# SCH___2022-11-09.net
KiCad netlist of a schematic drawn in EasyEDA
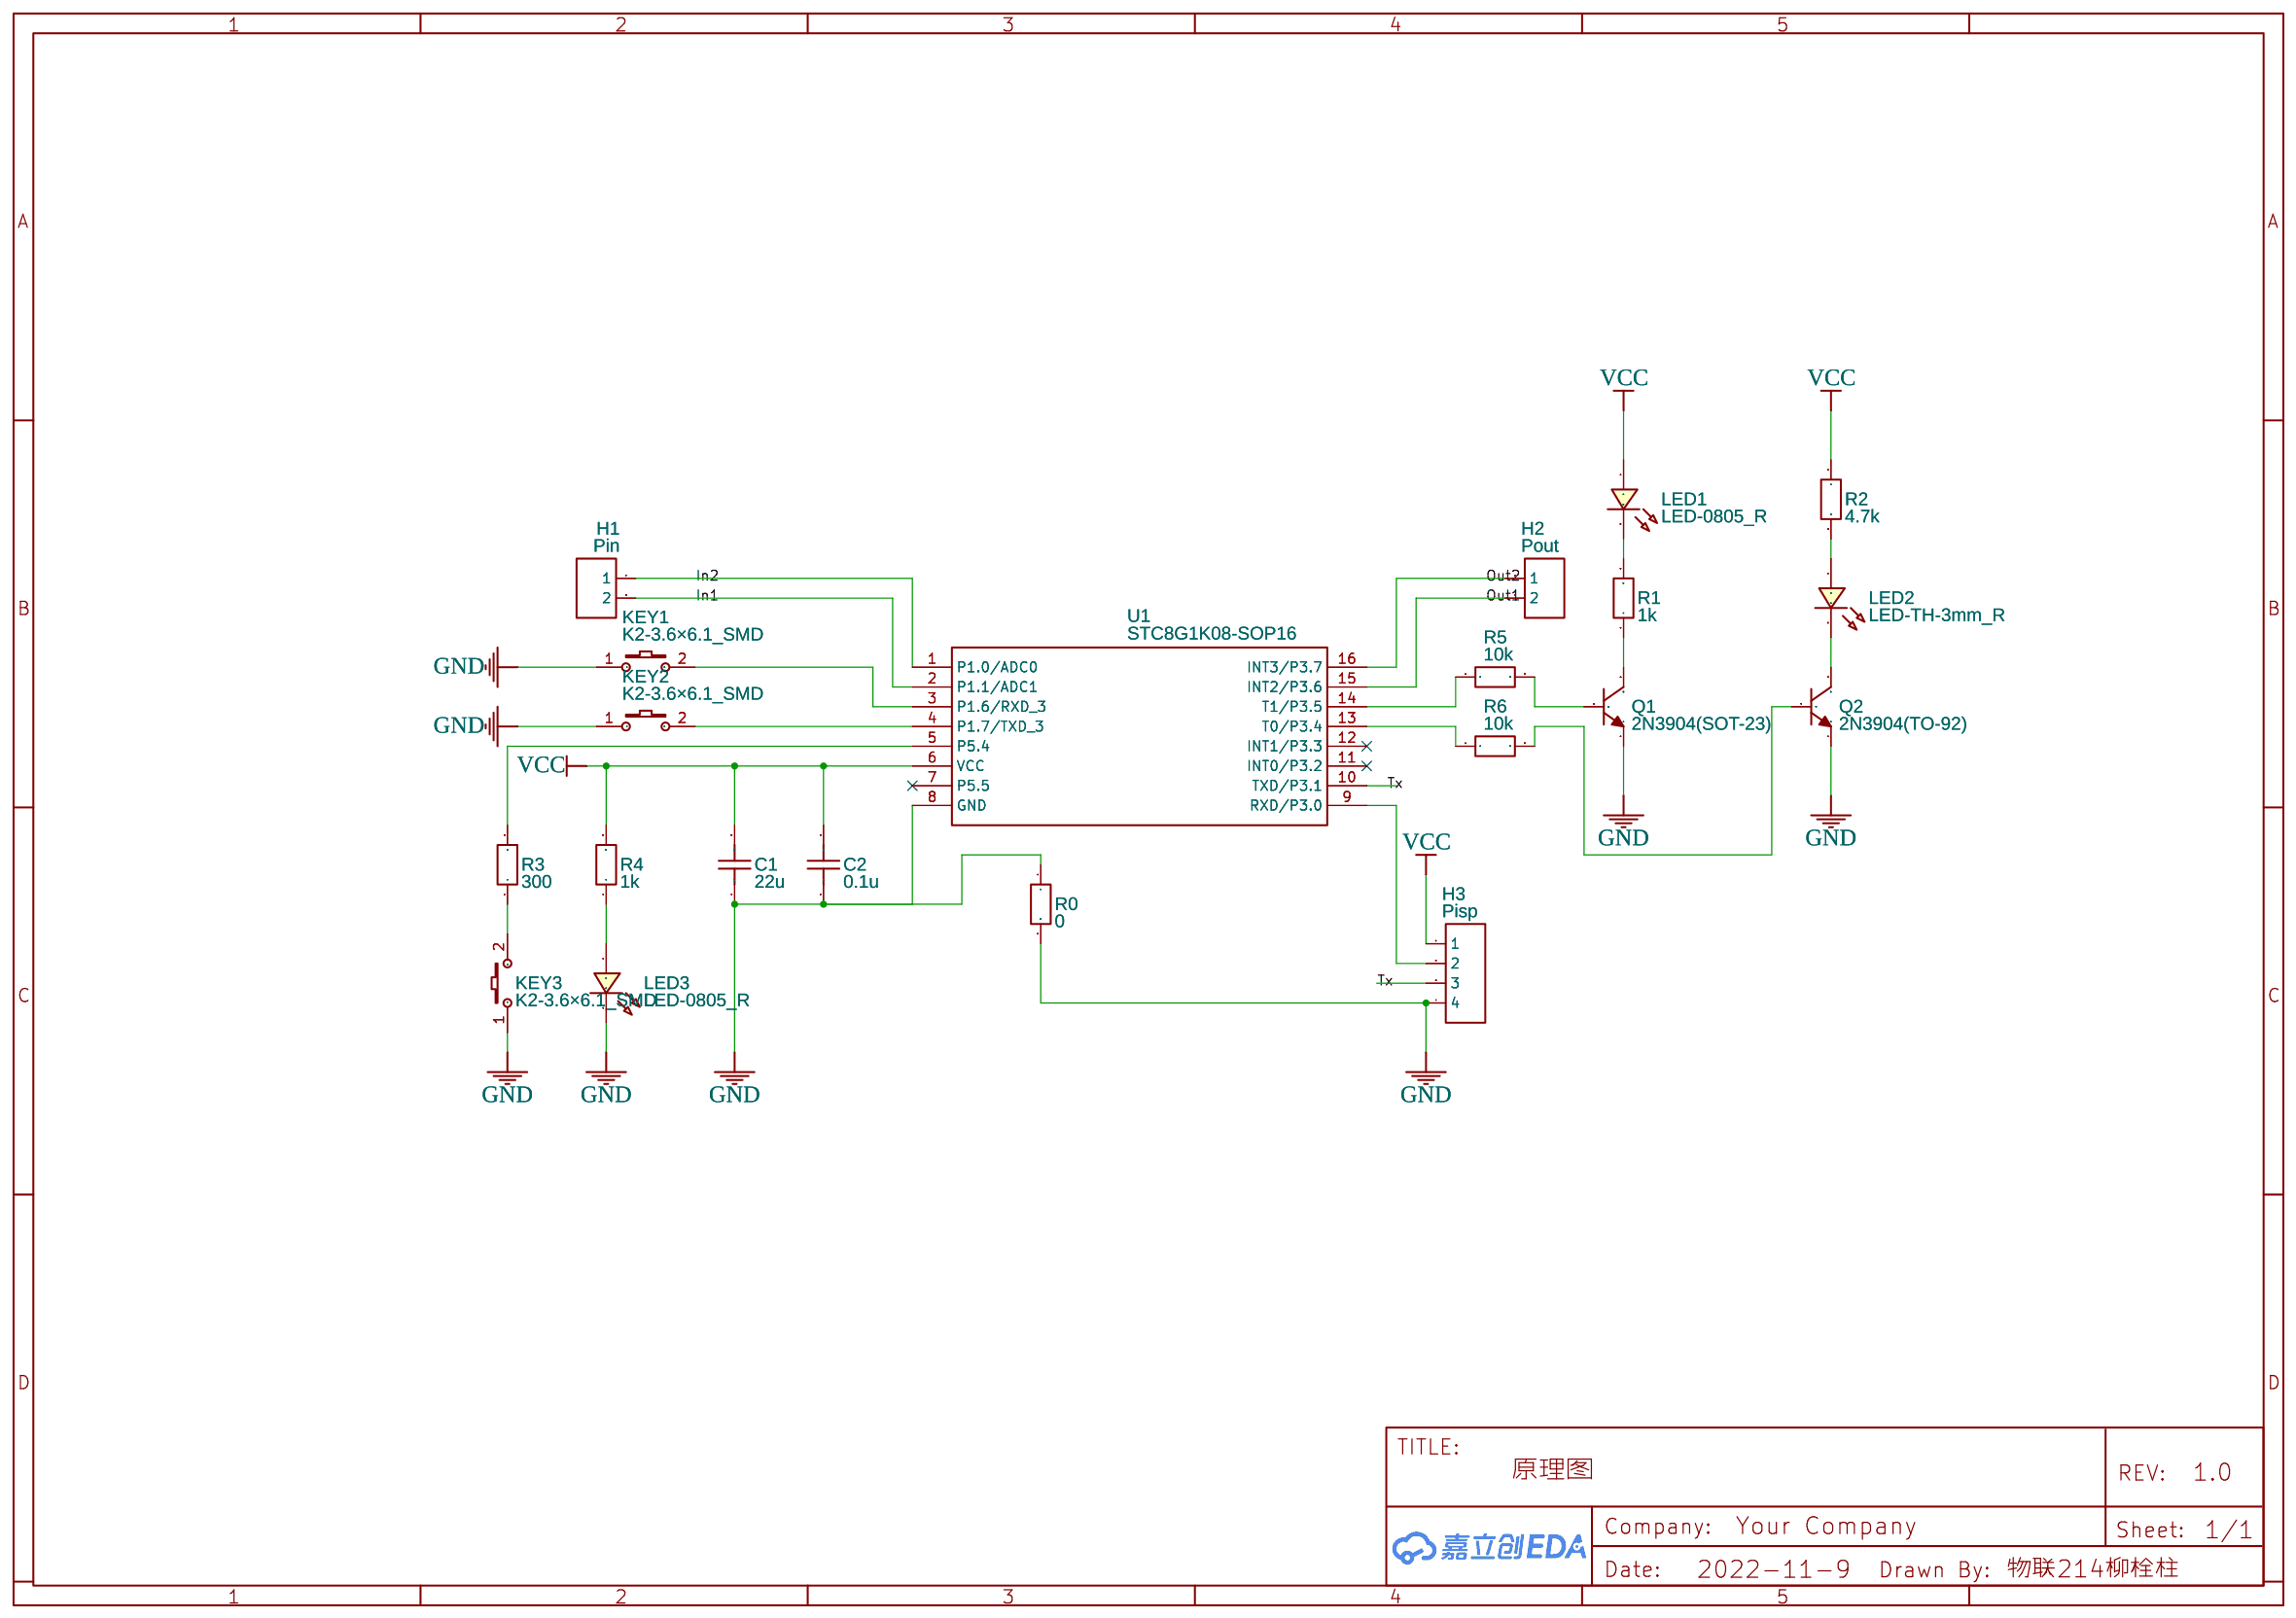
[diagram p0: schematic sheet]

(export (version "E")
  (design (tool "Eeschema 10.0.6"))
  (components
    (comp (ref "C1") (value "22u") (libsource (lib "") (part "C_0603_US")))
    (comp (ref "C2") (value "0.1u") (libsource (lib "") (part "C_0603_US")))
    (comp (ref "H1")
      (value "Pin")
      (fields (field (name "BOM_Supplier Part") "C49661"))
      (libsource (lib "") (part "HDR-F-2.54_1x2_1"))
    )
    (comp (ref "H2")
      (value "Pout")
      (fields (field (name "BOM_Supplier Part") "C49661"))
      (libsource (lib "") (part "HDR-F-2.54_1x2"))
    )
    (comp (ref "H3")
      (value "Pisp")
      (fields (field (name "BOM_Supplier Part") "C225501"))
      (libsource (lib "") (part "HDR-F-2.54_1x4"))
    )
    (comp (ref "KEY1")
      (value "K2-3.6×6.1_SMD")
      (fields
        (field (name "BOM_Manufacturer Part") "K2-1107ST-A4SW-06")
        (field (name "BOM_Supplier Part") "C118141")
      )
      (libsource (lib "") (part "K2-3.6×6.1_SMD_1"))
    )
    (comp (ref "KEY2")
      (value "K2-3.6×6.1_SMD")
      (fields
        (field (name "BOM_Manufacturer Part") "K2-1107ST-A4SW-06")
        (field (name "BOM_Supplier Part") "C118141")
      )
      (libsource (lib "") (part "K2-3.6×6.1_SMD_1"))
    )
    (comp (ref "KEY3")
      (value "K2-3.6×6.1_SMD")
      (fields
        (field (name "BOM_Manufacturer Part") "K2-1107ST-A4SW-06")
        (field (name "BOM_Supplier Part") "C118141")
      )
      (libsource (lib "") (part "K2-3.6×6.1_SMD"))
    )
    (comp (ref "LED1")
      (value "LED-0805_R")
      (fields
        (field (name "BOM_Manufacturer Part") "17-21SURC/S530-A3/TR8")
        (field (name "BOM_Supplier Part") "C72037")
      )
      (libsource (lib "") (part "LED-0805_R"))
    )
    (comp (ref "LED2")
      (value "LED-TH-3mm_R")
      (fields
        (field (name "BOM_Manufacturer Part") "204-10SDRD/S530-A3-L")
        (field (name "BOM_Supplier Part") "C84774")
      )
      (libsource (lib "") (part "LED-TH-3mm_R"))
    )
    (comp (ref "LED3")
      (value "LED-0805_R")
      (fields
        (field (name "BOM_Manufacturer Part") "17-21SURC/S530-A3/TR8")
        (field (name "BOM_Supplier Part") "C72037")
      )
      (libsource (lib "") (part "LED-0805_R"))
    )
    (comp (ref "Q1")
      (value "2N3904(SOT-23)")
      (fields
        (field (name "BOM_Manufacturer Part") "2n3904S-RTK/PS")
        (field (name "BOM_Supplier Part") "C18536")
      )
      (libsource (lib "") (part "2N3904(SOT-23)"))
    )
    (comp (ref "Q2")
      (value "2N3904(TO-92)")
      (fields (field (name "BOM_Manufacturer Part") "2N3904") (field (name "BOM_Supplier Part") "C118538"))
      (libsource (lib "") (part "2N3904(TO-92)"))
    )
    (comp (ref "R0") (value "0") (libsource (lib "") (part "R_0603_EU_1")))
    (comp (ref "R1") (value "1k") (libsource (lib "") (part "R_0603_EU_2")))
    (comp (ref "R2") (value "4.7k") (libsource (lib "") (part "R_0603_EU_1")))
    (comp (ref "R3") (value "300") (libsource (lib "") (part "R_0603_EU_2")))
    (comp (ref "R4") (value "1k") (libsource (lib "") (part "R_0603_EU_2")))
    (comp (ref "R5") (value "10k") (libsource (lib "") (part "R_0603_EU")))
    (comp (ref "R6") (value "10k") (libsource (lib "") (part "R_0603_EU")))
    (comp (ref "U1") (value "STC8G1K08-SOP16") (libsource (lib "") (part "STC8G1K08-SOP16")))
  )
  (nets
    (net (code "1") (name "/In1") (class "Default")
      (node (ref "H1") (pin "2") (pinfunction "2_2") (pintype "input"))
      (node (ref "U1") (pin "2") (pinfunction "P1.1/ADC1_2") (pintype "unspecified"))
    )
    (net (code "2") (name "/In2") (class "Default")
      (node (ref "H1") (pin "1") (pinfunction "1_1") (pintype "input"))
      (node (ref "U1") (pin "1") (pinfunction "P1.0/ADC0_1") (pintype "unspecified"))
    )
    (net (code "3") (name "/Out1") (class "Default")
      (node (ref "H2") (pin "2") (pinfunction "2_2") (pintype "input"))
      (node (ref "U1") (pin "15") (pinfunction "INT2/P3.6_15") (pintype "unspecified"))
    )
    (net (code "4") (name "/Out2") (class "Default")
      (node (ref "H2") (pin "1") (pinfunction "1_1") (pintype "input"))
      (node (ref "U1") (pin "16") (pinfunction "INT3/P3.7_16") (pintype "unspecified"))
    )
    (net (code "5") (name "/Tx") (class "Default")
      (node (ref "H3") (pin "3") (pinfunction "3_3") (pintype "unspecified"))
      (node (ref "U1") (pin "10") (pinfunction "TXD/P3.1_10") (pintype "unspecified"))
    )
    (net (code "6") (name "GND") (class "Default")
      (node (ref "C1") (pin "1") (pinfunction "1_1") (pintype "unspecified"))
      (node (ref "C2") (pin "1") (pinfunction "1_1") (pintype "unspecified"))
      (node (ref "H3") (pin "4") (pinfunction "4_4") (pintype "unspecified"))
      (node (ref "KEY1") (pin "1") (pinfunction "1_1") (pintype "unspecified"))
      (node (ref "KEY2") (pin "1") (pinfunction "1_1") (pintype "unspecified"))
      (node (ref "KEY3") (pin "1") (pinfunction "1_1") (pintype "unspecified"))
      (node (ref "LED3") (pin "2") (pinfunction "2_2") (pintype "unspecified"))
      (node (ref "Q1") (pin "1") (pinfunction "E_1") (pintype "input"))
      (node (ref "Q2") (pin "1") (pinfunction "E_1") (pintype "unspecified"))
      (node (ref "R0") (pin "1") (pinfunction "1_1") (pintype "unspecified"))
      (node (ref "R0") (pin "2") (pinfunction "2_2") (pintype "unspecified"))
      (node (ref "U1") (pin "8") (pinfunction "GND_8") (pintype "unspecified"))
    )
    (net (code "7") (name "Net-(KEY3-Pad2)") (class "Default")
      (node (ref "KEY3") (pin "2") (pinfunction "2_2") (pintype "unspecified"))
      (node (ref "R3") (pin "1") (pinfunction "1_1") (pintype "unspecified"))
    )
    (net (code "8") (name "Net-(LED1-Pad2)") (class "Default")
      (node (ref "LED1") (pin "2") (pinfunction "2_2") (pintype "unspecified"))
      (node (ref "R1") (pin "2") (pinfunction "2_2") (pintype "unspecified"))
    )
    (net (code "9") (name "Net-(LED2-Pad1)") (class "Default")
      (node (ref "LED2") (pin "1") (pinfunction "1_1") (pintype "unspecified"))
      (node (ref "R2") (pin "2") (pinfunction "2_2") (pintype "unspecified"))
    )
    (net (code "10") (name "Net-(LED3-Pad1)") (class "Default")
      (node (ref "LED3") (pin "1") (pinfunction "1_1") (pintype "unspecified"))
      (node (ref "R4") (pin "1") (pinfunction "1_1") (pintype "unspecified"))
    )
    (net (code "11") (name "Net-(Q1-B)") (class "Default")
      (node (ref "Q1") (pin "2") (pinfunction "B_2") (pintype "input"))
      (node (ref "R5") (pin "2") (pinfunction "2_2") (pintype "unspecified"))
    )
    (net (code "12") (name "Net-(Q1-C)") (class "Default")
      (node (ref "Q1") (pin "3") (pinfunction "C_3") (pintype "input"))
      (node (ref "R1") (pin "1") (pinfunction "1_1") (pintype "unspecified"))
    )
    (net (code "13") (name "Net-(Q2-B)") (class "Default")
      (node (ref "Q2") (pin "2") (pinfunction "B_2") (pintype "unspecified"))
      (node (ref "R6") (pin "2") (pinfunction "2_2") (pintype "unspecified"))
    )
    (net (code "14") (name "Net-(Q2-C)") (class "Default")
      (node (ref "LED2") (pin "2") (pinfunction "2_2") (pintype "unspecified"))
      (node (ref "Q2") (pin "3") (pinfunction "C_3") (pintype "unspecified"))
    )
    (net (code "15") (name "Net-(U1-P1.6{slash}RXD_3)") (class "Default")
      (node (ref "KEY1") (pin "2") (pinfunction "2_2") (pintype "unspecified"))
      (node (ref "U1") (pin "3") (pinfunction "P1.6/RXD_3_3") (pintype "unspecified"))
    )
    (net (code "16") (name "Net-(U1-P1.7{slash}TXD_3)") (class "Default")
      (node (ref "KEY2") (pin "2") (pinfunction "2_2") (pintype "unspecified"))
      (node (ref "U1") (pin "4") (pinfunction "P1.7/TXD_3_4") (pintype "unspecified"))
    )
    (net (code "17") (name "Net-(U1-P5.4)") (class "Default")
      (node (ref "R3") (pin "2") (pinfunction "2_2") (pintype "unspecified"))
      (node (ref "U1") (pin "5") (pinfunction "P5.4_5") (pintype "unspecified"))
    )
    (net (code "18") (name "Net-(U1-RXD{slash}P3.0)") (class "Default")
      (node (ref "H3") (pin "2") (pinfunction "2_2") (pintype "unspecified"))
      (node (ref "U1") (pin "9") (pinfunction "RXD/P3.0_9") (pintype "unspecified"))
    )
    (net (code "19") (name "Net-(U1-T0{slash}P3.4)") (class "Default")
      (node (ref "R6") (pin "1") (pinfunction "1_1") (pintype "unspecified"))
      (node (ref "U1") (pin "13") (pinfunction "T0/P3.4_13") (pintype "unspecified"))
    )
    (net (code "20") (name "Net-(U1-T1{slash}P3.5)") (class "Default")
      (node (ref "R5") (pin "1") (pinfunction "1_1") (pintype "unspecified"))
      (node (ref "U1") (pin "14") (pinfunction "T1/P3.5_14") (pintype "unspecified"))
    )
    (net (code "21") (name "VCC") (class "Default")
      (node (ref "C1") (pin "2") (pinfunction "2_2") (pintype "unspecified"))
      (node (ref "C2") (pin "2") (pinfunction "2_2") (pintype "unspecified"))
      (node (ref "H3") (pin "1") (pinfunction "1_1") (pintype "unspecified"))
      (node (ref "LED1") (pin "1") (pinfunction "1_1") (pintype "unspecified"))
      (node (ref "R2") (pin "1") (pinfunction "1_1") (pintype "unspecified"))
      (node (ref "R4") (pin "2") (pinfunction "2_2") (pintype "unspecified"))
      (node (ref "U1") (pin "6") (pinfunction "VCC_6") (pintype "unspecified"))
    )
    (net (code "22") (name "unconnected-(U1-INT0{slash}P3.2-Pad11)") (class "Default")
      (node (ref "U1") (pin "11") (pinfunction "INT0/P3.2_11") (pintype "unspecified+no_connect"))
    )
    (net (code "23") (name "unconnected-(U1-INT1{slash}P3.3-Pad12)") (class "Default")
      (node (ref "U1") (pin "12") (pinfunction "INT1/P3.3_12") (pintype "unspecified+no_connect"))
    )
    (net (code "24") (name "unconnected-(U1-P5.5-Pad7)") (class "Default")
      (node (ref "U1") (pin "7") (pinfunction "P5.5_7") (pintype "unspecified+no_connect"))
    )
  )
)
